# RPi_ADC_hat.net
KiCad netlist of a schematic drawn in EAGLE
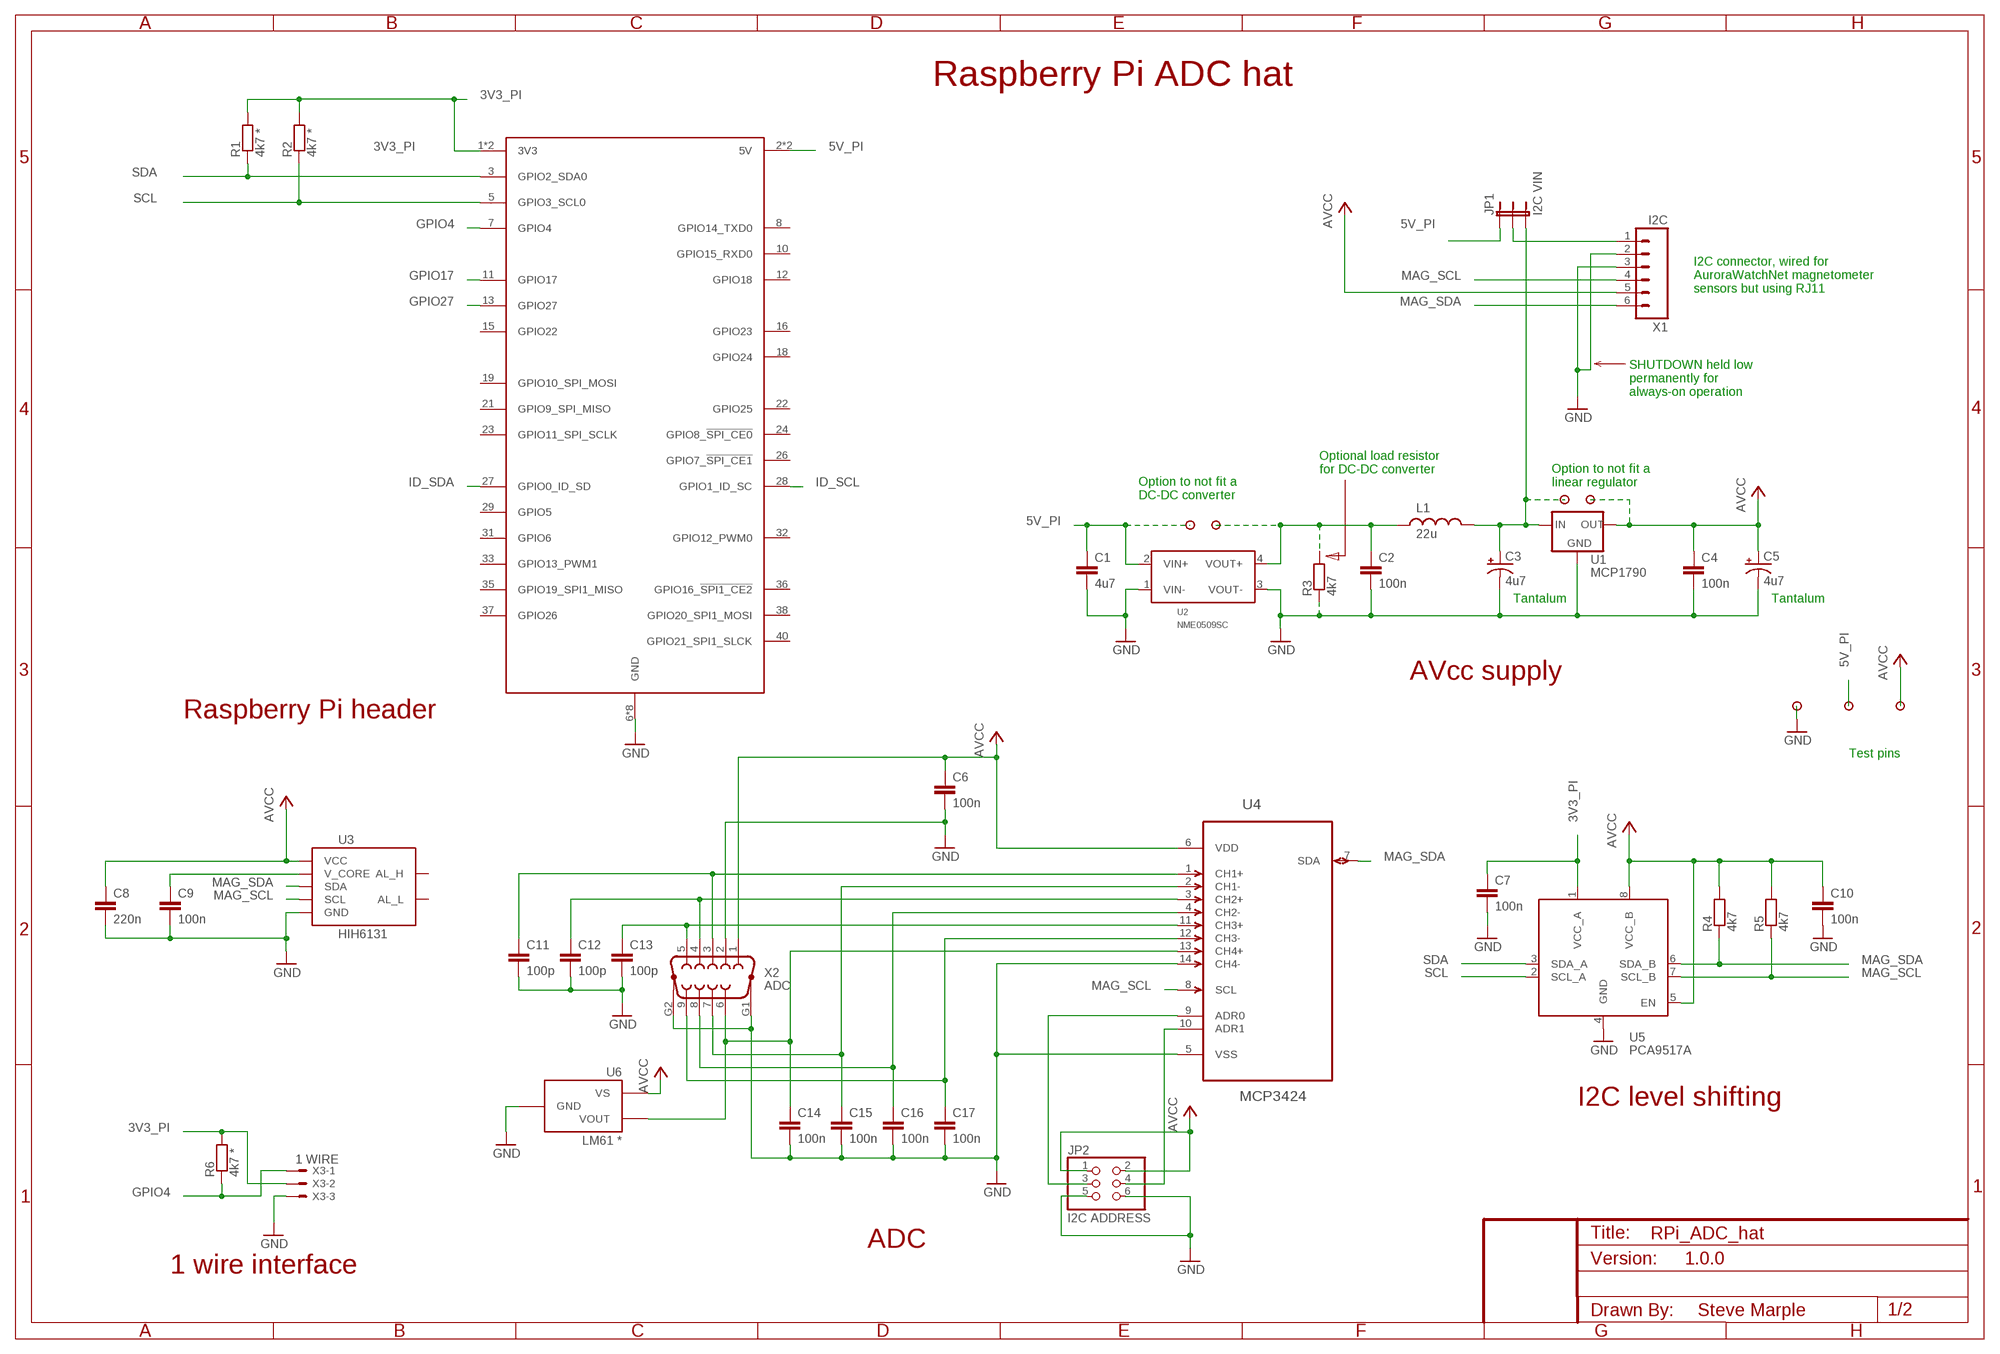
[diagram p0: schematic, sheet 1]
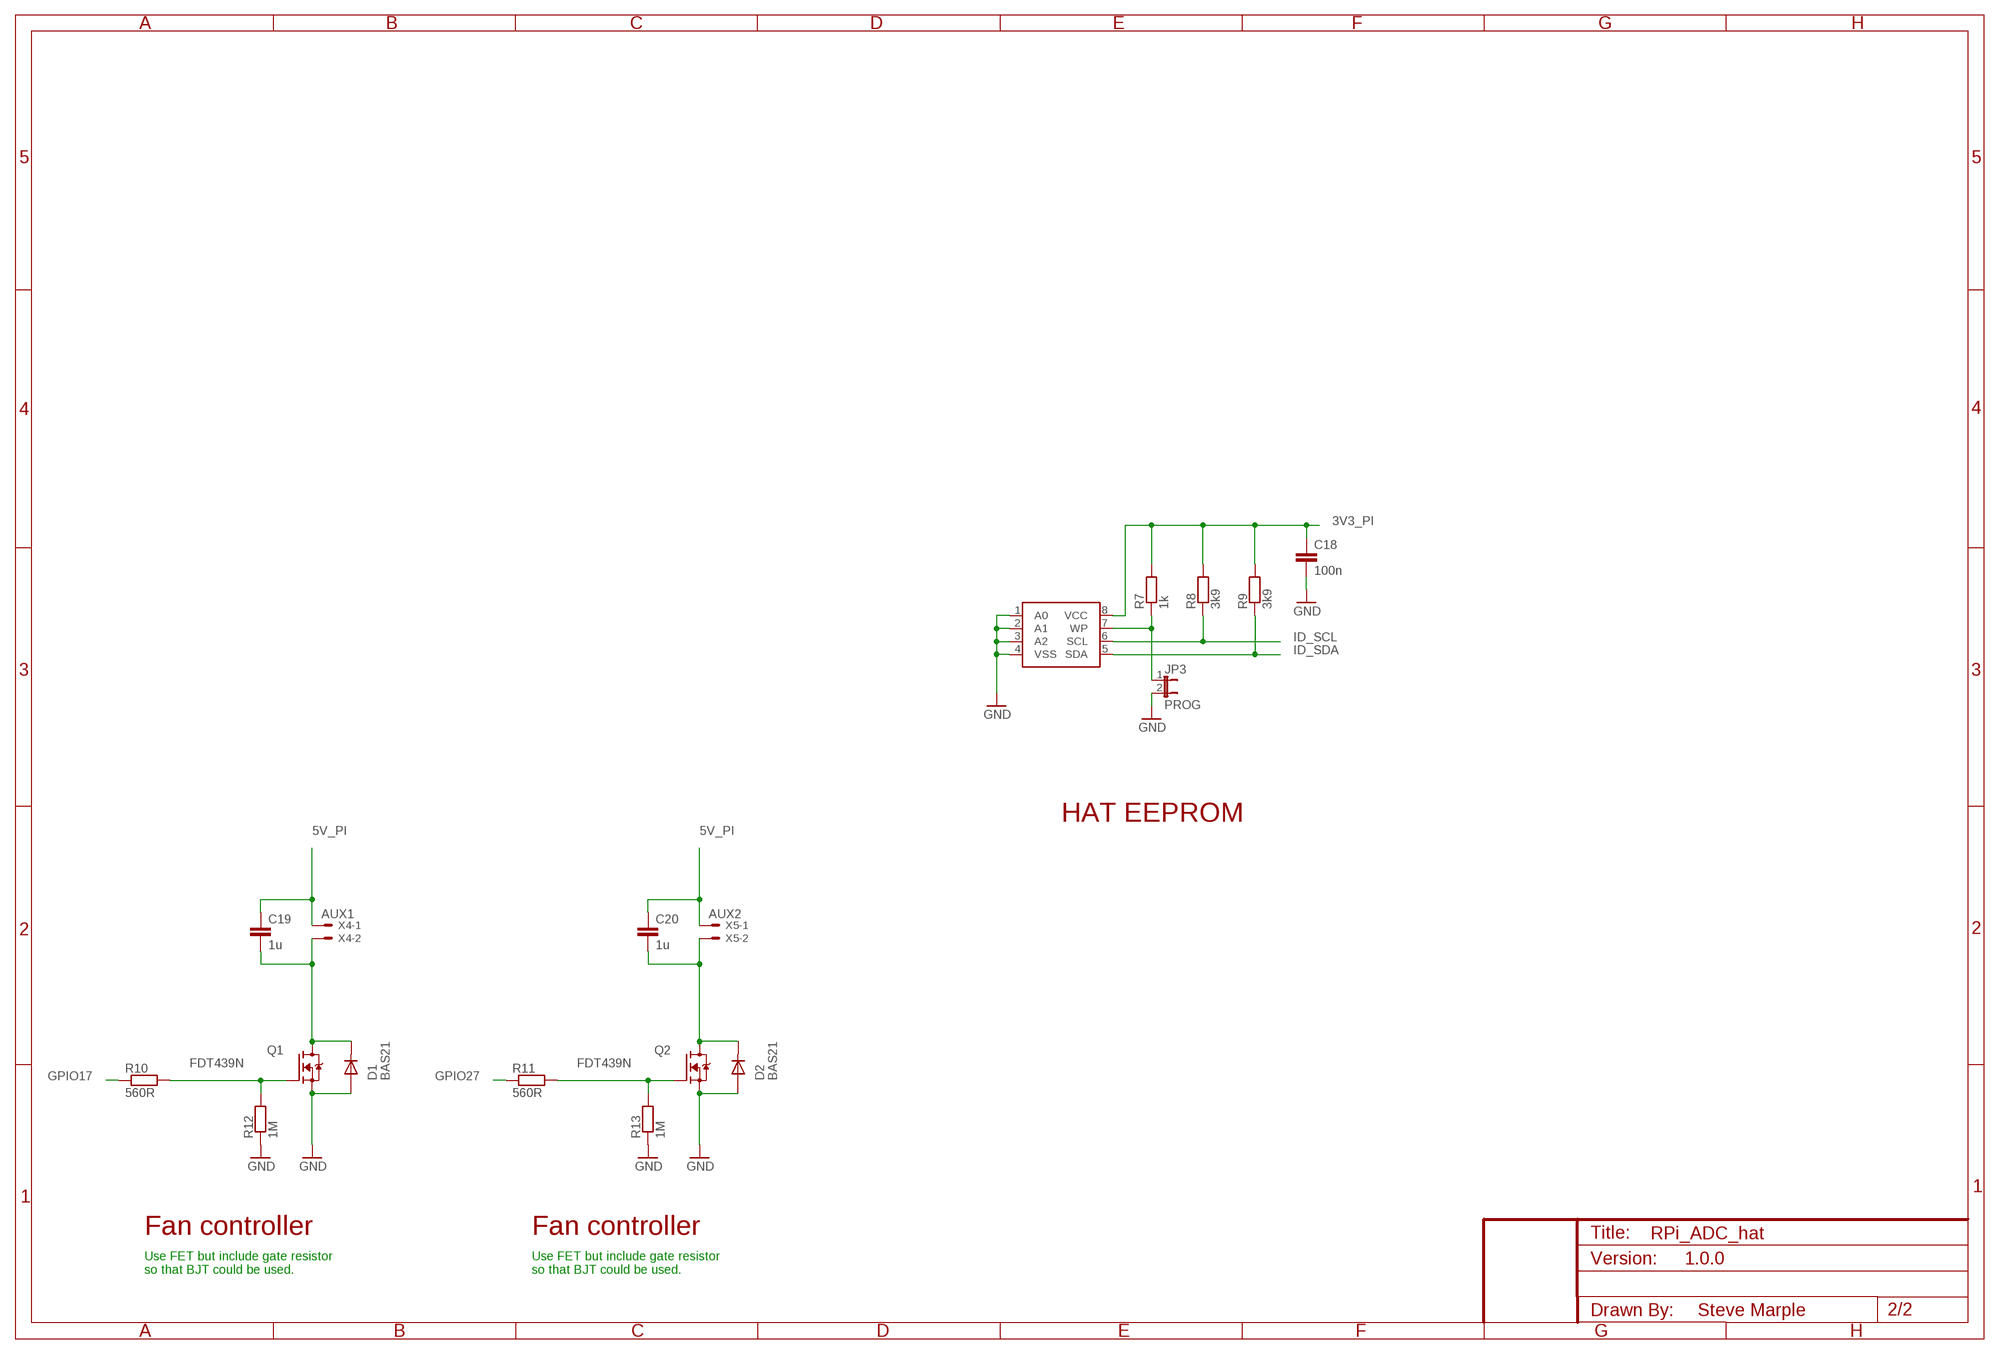
[diagram p1: schematic, sheet 2]

(export (version "E")
  (design (tool "Eeschema 10.0.6"))
  (components
    (comp (ref "C1")
      (value "4u7")
      (footprint "eagle-import:1206-HAND")
      (libsource (lib "eagle-import") (part "C-EU1206-HAND"))
    )
    (comp (ref "C2")
      (value "100n")
      (footprint "eagle-import:1206-HAND")
      (libsource (lib "eagle-import") (part "C-EU1206-HAND"))
    )
    (comp (ref "C3")
      (value "4u7")
      (footprint "eagle-import:CPOL-1210-HAND")
      (libsource (lib "eagle-import") (part "CAP_POL1210-HAND"))
    )
    (comp (ref "C4")
      (value "100n")
      (footprint "eagle-import:1206-HAND")
      (libsource (lib "eagle-import") (part "C-EU1206-HAND"))
    )
    (comp (ref "C5")
      (value "4u7")
      (footprint "eagle-import:CPOL-1210-HAND")
      (libsource (lib "eagle-import") (part "CAP_POL1210-HAND"))
    )
    (comp (ref "C6")
      (value "100n")
      (footprint "eagle-import:1206-HAND")
      (libsource (lib "eagle-import") (part "C-EU1206-HAND"))
    )
    (comp (ref "C7")
      (value "100n")
      (footprint "eagle-import:1206-HAND")
      (libsource (lib "eagle-import") (part "C-EU1206-HAND"))
    )
    (comp (ref "C8")
      (value "220n")
      (footprint "eagle-import:1206-HAND")
      (libsource (lib "eagle-import") (part "C-EU1206-HAND"))
    )
    (comp (ref "C9")
      (value "100n")
      (footprint "eagle-import:1206-HAND")
      (libsource (lib "eagle-import") (part "C-EU1206-HAND"))
    )
    (comp (ref "C10")
      (value "100n")
      (footprint "eagle-import:1206-HAND")
      (libsource (lib "eagle-import") (part "C-EU1206-HAND"))
    )
    (comp (ref "C11")
      (value "100p")
      (footprint "eagle-import:1206-HAND")
      (libsource (lib "eagle-import") (part "C-EU1206-HAND"))
    )
    (comp (ref "C12")
      (value "100p")
      (footprint "eagle-import:1206-HAND")
      (libsource (lib "eagle-import") (part "C-EU1206-HAND"))
    )
    (comp (ref "C13")
      (value "100p")
      (footprint "eagle-import:1206-HAND")
      (libsource (lib "eagle-import") (part "C-EU1206-HAND"))
    )
    (comp (ref "C14")
      (value "100n")
      (footprint "eagle-import:1206-HAND")
      (libsource (lib "eagle-import") (part "C-EU1206-HAND"))
    )
    (comp (ref "C15")
      (value "100n")
      (footprint "eagle-import:1206-HAND")
      (libsource (lib "eagle-import") (part "C-EU1206-HAND"))
    )
    (comp (ref "C16")
      (value "100n")
      (footprint "eagle-import:1206-HAND")
      (libsource (lib "eagle-import") (part "C-EU1206-HAND"))
    )
    (comp (ref "C17")
      (value "100n")
      (footprint "eagle-import:1206-HAND")
      (libsource (lib "eagle-import") (part "C-EU1206-HAND"))
    )
    (comp (ref "JP1")
      (value "I2C VIN")
      (footprint "eagle-import:1X03")
      (libsource (lib "eagle-import") (part "JUMPER-3PTH"))
    )
    (comp (ref "JP2")
      (value "I2C ADDRESS")
      (footprint "eagle-import:2X03")
      (libsource (lib "eagle-import") (part "PINHD-2X3"))
    )
    (comp (ref "L1")
      (value "22u")
      (footprint "eagle-import:1210-HAND")
      (libsource (lib "eagle-import") (part "INDUCTOR1210-HAND"))
    )
    (comp (ref "R1")
      (value "4k7 *")
      (footprint "eagle-import:1206-HAND")
      (libsource (lib "eagle-import") (part "RESISTOR1206-HAND"))
    )
    (comp (ref "R2")
      (value "4k7 *")
      (footprint "eagle-import:1206-HAND")
      (libsource (lib "eagle-import") (part "RESISTOR1206-HAND"))
    )
    (comp (ref "R3")
      (value "4k7")
      (footprint "eagle-import:1210-HAND")
      (libsource (lib "eagle-import") (part "RESISTOR1210-HAND"))
    )
    (comp (ref "R4")
      (value "4k7")
      (footprint "eagle-import:1206-HAND")
      (libsource (lib "eagle-import") (part "RESISTOR1206-HAND"))
    )
    (comp (ref "R5")
      (value "4k7")
      (footprint "eagle-import:1206-HAND")
      (libsource (lib "eagle-import") (part "RESISTOR1206-HAND"))
    )
    (comp (ref "R6")
      (value "4k7 *")
      (footprint "eagle-import:1206-HAND")
      (libsource (lib "eagle-import") (part "RESISTOR1206-HAND"))
    )
    (comp (ref "U$1")
      (value "PCB")
      (footprint "eagle-import:RASPBERRY-PI-3")
      (libsource (lib "eagle-import") (part "RASPBERRY-PI-3"))
    )
    (comp (ref "U$2")
      (value "PAD")
      (footprint "eagle-import:PAD")
      (libsource (lib "eagle-import") (part "PAD"))
    )
    (comp (ref "U$3")
      (value "PAD")
      (footprint "eagle-import:PAD")
      (libsource (lib "eagle-import") (part "PAD"))
    )
    (comp (ref "U$4")
      (value "PAD")
      (footprint "eagle-import:PAD")
      (libsource (lib "eagle-import") (part "PAD"))
    )
    (comp (ref "U$5")
      (value "PAD")
      (footprint "eagle-import:PAD")
      (libsource (lib "eagle-import") (part "PAD"))
    )
    (comp (ref "U$6")
      (value "PAD")
      (footprint "eagle-import:PAD")
      (libsource (lib "eagle-import") (part "PAD"))
    )
    (comp (ref "U$7")
      (value "PAD")
      (footprint "eagle-import:PAD")
      (libsource (lib "eagle-import") (part "PAD"))
    )
    (comp (ref "U$8")
      (value "PAD")
      (footprint "eagle-import:PAD")
      (libsource (lib "eagle-import") (part "PAD"))
    )
    (comp (ref "U1")
      (value "MCP1790")
      (footprint "eagle-import:SOT223-HAND")
      (libsource (lib "eagle-import") (part "TC1262SOT223-HAND"))
    )
    (comp (ref "U2")
      (value "NME0509SC")
      (footprint "eagle-import:DC-DC-MURATA-NME-05-12-SERIES")
      (libsource (lib "eagle-import") (part "DC-DC-CONV-4PIN-ISOLATINGMURATA-NME-05-12-SERIES"))
    )
    (comp (ref "U3")
      (value "HIH6131")
      (footprint "eagle-import:SO08")
      (libsource (lib "eagle-import") (part "HONEYWELL-HIH613XSOIC8"))
    )
    (comp (ref "U4")
      (value "MCP3424")
      (footprint "eagle-import:SO14")
      (libsource (lib "eagle-import") (part "MCP3424-E/SLSO14"))
    )
    (comp (ref "U5")
      (value "PCA9517A")
      (footprint "eagle-import:SO08")
      (libsource (lib "eagle-import") (part "PCA9517ASOIC"))
    )
    (comp (ref "U6")
      (value "LM61 *")
      (footprint "eagle-import:SOT23-3-HAND")
      (libsource (lib "eagle-import") (part "LM61SOT23"))
    )
    (comp (ref "X1")
      (value "I2C")
      (footprint "eagle-import:RJ11-6")
      (libsource (lib "eagle-import") (part "RJ11-6PTH"))
    )
    (comp (ref "X2")
      (value "ADC")
      (footprint "eagle-import:DSUB-5504F1-02-9PIN")
      (libsource (lib "eagle-import") (part "CONN-D9-FEMALEMULTICOMP-5504F1"))
    )
    (comp (ref "X3")
      (value "1 WIRE")
      (footprint "eagle-import:22-23-2031")
      (fields (field (name "MF") "MOLEX") (field (name "MPN") "22-23-2031"))
      (libsource (lib "eagle-import") (part "22-23-2031"))
    )
    (comp (ref "C18")
      (value "100n")
      (footprint "eagle-import:1206-HAND")
      (libsource (lib "eagle-import") (part "C-EU1206-HAND"))
    )
    (comp (ref "C19")
      (value "1u")
      (footprint "eagle-import:1206-HAND")
      (libsource (lib "eagle-import") (part "C-EU1206-HAND"))
    )
    (comp (ref "C20")
      (value "1u")
      (footprint "eagle-import:1206-HAND")
      (libsource (lib "eagle-import") (part "C-EU1206-HAND"))
    )
    (comp (ref "D1")
      (value "BAS21")
      (footprint "eagle-import:SOT23-3-HAND")
      (libsource (lib "eagle-import") (part "DIODESOT23-1-3-HAND"))
    )
    (comp (ref "D2")
      (value "BAS21")
      (footprint "eagle-import:SOT23-3-HAND")
      (libsource (lib "eagle-import") (part "DIODESOT23-1-3-HAND"))
    )
    (comp (ref "JP3")
      (value "PROG")
      (footprint "eagle-import:1X02")
      (libsource (lib "eagle-import") (part "JUMPER-2PTH"))
    )
    (comp (ref "Q1")
      (value "FDT439N")
      (footprint "eagle-import:SOT223-HAND")
      (libsource (lib "eagle-import") (part "FET-N-TYPESOT223-HAND"))
    )
    (comp (ref "Q2")
      (value "FDT439N")
      (footprint "eagle-import:SOT223-HAND")
      (libsource (lib "eagle-import") (part "FET-N-TYPESOT223-HAND"))
    )
    (comp (ref "R7")
      (value "1k")
      (footprint "eagle-import:1206-HAND")
      (libsource (lib "eagle-import") (part "RESISTOR1206-HAND"))
    )
    (comp (ref "R8")
      (value "3k9")
      (footprint "eagle-import:1206-HAND")
      (libsource (lib "eagle-import") (part "RESISTOR1206-HAND"))
    )
    (comp (ref "R9")
      (value "3k9")
      (footprint "eagle-import:1206-HAND")
      (libsource (lib "eagle-import") (part "RESISTOR1206-HAND"))
    )
    (comp (ref "R10")
      (value "560R")
      (footprint "eagle-import:1206-HAND")
      (libsource (lib "eagle-import") (part "RESISTOR1206-HAND"))
    )
    (comp (ref "R11")
      (value "560R")
      (footprint "eagle-import:1206-HAND")
      (libsource (lib "eagle-import") (part "RESISTOR1206-HAND"))
    )
    (comp (ref "R12")
      (value "1M")
      (footprint "eagle-import:1206-HAND")
      (libsource (lib "eagle-import") (part "RESISTOR1206-HAND"))
    )
    (comp (ref "R13")
      (value "1M")
      (footprint "eagle-import:1206-HAND")
      (libsource (lib "eagle-import") (part "RESISTOR1206-HAND"))
    )
    (comp (ref "U7")
      (value "C24C32")
      (footprint "eagle-import:SO08")
      (libsource (lib "eagle-import") (part "EEPROM-C24CXXSOIC8"))
    )
    (comp (ref "X4")
      (value "AUX1")
      (footprint "eagle-import:22-23-2021")
      (fields (field (name "MF") "MOLEX") (field (name "MPN") "22-23-2021"))
      (libsource (lib "eagle-import") (part "22-23-2021"))
    )
    (comp (ref "X5")
      (value "AUX2")
      (footprint "eagle-import:22-23-2021")
      (fields (field (name "MF") "MOLEX") (field (name "MPN") "22-23-2021"))
      (libsource (lib "eagle-import") (part "22-23-2021"))
    )
  )
  (nets
    (net (code "1") (name "3V3_PI") (class "Default")
      (node (ref "C18") (pin "1") (pinfunction "1_1") (pintype "passive"))
      (node (ref "C7") (pin "1") (pinfunction "1_1") (pintype "passive"))
      (node (ref "R1") (pin "2") (pinfunction "2_2") (pintype "passive"))
      (node (ref "R2") (pin "2") (pinfunction "2_2") (pintype "passive"))
      (node (ref "R6") (pin "2") (pinfunction "2_2") (pintype "passive"))
      (node (ref "R7") (pin "2") (pinfunction "2_2") (pintype "passive"))
      (node (ref "R8") (pin "2") (pinfunction "2_2") (pintype "passive"))
      (node (ref "R9") (pin "2") (pinfunction "2_2") (pintype "passive"))
      (node (ref "U$1") (pin "1") (pinfunction "3V3_1") (pintype "bidirectional"))
      (node (ref "U$1") (pin "17") (pinfunction "3V3_17") (pintype "bidirectional"))
      (node (ref "U5") (pin "1") (pinfunction "VCC_A_1") (pintype "power_in"))
      (node (ref "U7") (pin "8") (pinfunction "VCC_8") (pintype "power_in"))
      (node (ref "X3") (pin "2") (pinfunction "S_2") (pintype "passive"))
    )
    (net (code "2") (name "5V_PI") (class "Default")
      (node (ref "C1") (pin "1") (pinfunction "1_1") (pintype "passive"))
      (node (ref "C19") (pin "1") (pinfunction "1_1") (pintype "passive"))
      (node (ref "C20") (pin "1") (pinfunction "1_1") (pintype "passive"))
      (node (ref "JP1") (pin "1") (pinfunction "1_1") (pintype "passive"))
      (node (ref "U$1") (pin "2") (pinfunction "5V_2") (pintype "bidirectional"))
      (node (ref "U$1") (pin "4") (pinfunction "5V_4") (pintype "bidirectional"))
      (node (ref "U$4") (pin "1") (pinfunction "1_1") (pintype "bidirectional"))
      (node (ref "U$7") (pin "1") (pinfunction "1_1") (pintype "bidirectional"))
      (node (ref "U2") (pin "2") (pinfunction "VIN+_2") (pintype "bidirectional"))
      (node (ref "X4") (pin "1") (pinfunction "S_1") (pintype "passive"))
      (node (ref "X5") (pin "1") (pinfunction "S_1") (pintype "passive"))
    )
    (net (code "3") (name "AVCC") (class "Default")
      (node (ref "C10") (pin "1") (pinfunction "1_1") (pintype "passive"))
      (node (ref "C4") (pin "1") (pinfunction "1_1") (pintype "passive"))
      (node (ref "C5") (pin "+") (pinfunction "+_+") (pintype "passive"))
      (node (ref "C6") (pin "1") (pinfunction "1_1") (pintype "passive"))
      (node (ref "C8") (pin "1") (pinfunction "1_1") (pintype "passive"))
      (node (ref "JP2") (pin "1") (pinfunction "1_1") (pintype "passive"))
      (node (ref "JP2") (pin "2") (pinfunction "2_2") (pintype "passive"))
      (node (ref "R4") (pin "2") (pinfunction "2_2") (pintype "passive"))
      (node (ref "R5") (pin "2") (pinfunction "2_2") (pintype "passive"))
      (node (ref "U$3") (pin "1") (pinfunction "1_1") (pintype "bidirectional"))
      (node (ref "U$8") (pin "1") (pinfunction "1_1") (pintype "bidirectional"))
      (node (ref "U1") (pin "3") (pinfunction "OUT_3") (pintype "power_in"))
      (node (ref "U3") (pin "8") (pinfunction "VCC_8") (pintype "power_in"))
      (node (ref "U4") (pin "6") (pinfunction "VDD_6") (pintype "power_in"))
      (node (ref "U5") (pin "5") (pinfunction "EN_5") (pintype "bidirectional"))
      (node (ref "U5") (pin "8") (pinfunction "VCC_B_8") (pintype "power_in"))
      (node (ref "U6") (pin "1") (pinfunction "VS_1") (pintype "bidirectional"))
      (node (ref "X1") (pin "5") (pinfunction "5_5") (pintype "passive"))
      (node (ref "X2") (pin "1") (pinfunction "1_1") (pintype "passive"))
    )
    (net (code "4") (name "GND") (class "Default")
      (node (ref "C1") (pin "2") (pinfunction "2_2") (pintype "passive"))
      (node (ref "C10") (pin "2") (pinfunction "2_2") (pintype "passive"))
      (node (ref "C11") (pin "2") (pinfunction "2_2") (pintype "passive"))
      (node (ref "C12") (pin "2") (pinfunction "2_2") (pintype "passive"))
      (node (ref "C13") (pin "2") (pinfunction "2_2") (pintype "passive"))
      (node (ref "C14") (pin "2") (pinfunction "2_2") (pintype "passive"))
      (node (ref "C15") (pin "2") (pinfunction "2_2") (pintype "passive"))
      (node (ref "C16") (pin "2") (pinfunction "2_2") (pintype "passive"))
      (node (ref "C17") (pin "2") (pinfunction "2_2") (pintype "passive"))
      (node (ref "C18") (pin "2") (pinfunction "2_2") (pintype "passive"))
      (node (ref "C2") (pin "2") (pinfunction "2_2") (pintype "passive"))
      (node (ref "C3") (pin "-") (pinfunction "-_-") (pintype "passive"))
      (node (ref "C4") (pin "2") (pinfunction "2_2") (pintype "passive"))
      (node (ref "C5") (pin "-") (pinfunction "-_-") (pintype "passive"))
      (node (ref "C6") (pin "2") (pinfunction "2_2") (pintype "passive"))
      (node (ref "C7") (pin "2") (pinfunction "2_2") (pintype "passive"))
      (node (ref "C8") (pin "2") (pinfunction "2_2") (pintype "passive"))
      (node (ref "C9") (pin "2") (pinfunction "2_2") (pintype "passive"))
      (node (ref "D1") (pin "1") (pinfunction "A_1") (pintype "passive"))
      (node (ref "D2") (pin "1") (pinfunction "A_1") (pintype "passive"))
      (node (ref "JP2") (pin "5") (pinfunction "5_5") (pintype "passive"))
      (node (ref "JP2") (pin "6") (pinfunction "6_6") (pintype "passive"))
      (node (ref "JP3") (pin "2") (pinfunction "2_2") (pintype "passive"))
      (node (ref "Q1") (pin "3") (pinfunction "S_3") (pintype "passive"))
      (node (ref "Q2") (pin "3") (pinfunction "S_3") (pintype "passive"))
      (node (ref "R12") (pin "1") (pinfunction "1_1") (pintype "passive"))
      (node (ref "R13") (pin "1") (pinfunction "1_1") (pintype "passive"))
      (node (ref "R3") (pin "1") (pinfunction "1_1") (pintype "passive"))
      (node (ref "U$1") (pin "14") (pinfunction "GND_14") (pintype "bidirectional"))
      (node (ref "U$1") (pin "20") (pinfunction "GND_20") (pintype "bidirectional"))
      (node (ref "U$1") (pin "25") (pinfunction "GND_25") (pintype "bidirectional"))
      (node (ref "U$1") (pin "30") (pinfunction "GND_30") (pintype "bidirectional"))
      (node (ref "U$1") (pin "34") (pinfunction "GND_34") (pintype "bidirectional"))
      (node (ref "U$1") (pin "39") (pinfunction "GND_39") (pintype "bidirectional"))
      (node (ref "U$1") (pin "6") (pinfunction "GND_6") (pintype "bidirectional"))
      (node (ref "U$1") (pin "9") (pinfunction "GND_9") (pintype "bidirectional"))
      (node (ref "U$6") (pin "1") (pinfunction "1_1") (pintype "bidirectional"))
      (node (ref "U1") (pin "2") (pinfunction "GND_2") (pintype "power_in"))
      (node (ref "U1") (pin "4") (pinfunction "GND_4") (pintype "power_in"))
      (node (ref "U2") (pin "1") (pinfunction "VIN-_1") (pintype "bidirectional"))
      (node (ref "U2") (pin "3") (pinfunction "VOUT-_3") (pintype "bidirectional"))
      (node (ref "U3") (pin "2") (pinfunction "GND_2") (pintype "power_in"))
      (node (ref "U4") (pin "14") (pinfunction "CH4-_14") (pintype "input"))
      (node (ref "U4") (pin "5") (pinfunction "VSS_5") (pintype "power_in"))
      (node (ref "U5") (pin "4") (pinfunction "GND_4") (pintype "power_in"))
      (node (ref "U6") (pin "3") (pinfunction "GND_3") (pintype "bidirectional"))
      (node (ref "U7") (pin "1") (pinfunction "A0_1") (pintype "input"))
      (node (ref "U7") (pin "2") (pinfunction "A1_2") (pintype "input"))
      (node (ref "U7") (pin "3") (pinfunction "A2_3") (pintype "input"))
      (node (ref "U7") (pin "4") (pinfunction "VSS_4") (pintype "power_in"))
      (node (ref "X1") (pin "2") (pinfunction "2_2") (pintype "passive"))
      (node (ref "X1") (pin "3") (pinfunction "3_3") (pintype "passive"))
      (node (ref "X2") (pin "2") (pinfunction "2_2") (pintype "passive"))
      (node (ref "X2") (pin "G1") (pinfunction "G1_G1") (pintype "passive"))
      (node (ref "X2") (pin "G2") (pinfunction "G2_G2") (pintype "passive"))
      (node (ref "X3") (pin "3") (pinfunction "S_3") (pintype "passive"))
    )
    (net (code "5") (name "GPIO4") (class "Default")
      (node (ref "R6") (pin "1") (pinfunction "1_1") (pintype "passive"))
      (node (ref "U$1") (pin "7") (pinfunction "GPIO4_7") (pintype "bidirectional"))
      (node (ref "X3") (pin "1") (pinfunction "S_1") (pintype "passive"))
    )
    (net (code "6") (name "GPIO17") (class "Default")
      (node (ref "R10") (pin "1") (pinfunction "1_1") (pintype "passive"))
      (node (ref "U$1") (pin "11") (pinfunction "GPIO17_11") (pintype "bidirectional"))
    )
    (net (code "7") (name "GPIO27") (class "Default")
      (node (ref "R11") (pin "1") (pinfunction "1_1") (pintype "passive"))
      (node (ref "U$1") (pin "13") (pinfunction "GPIO27_13") (pintype "bidirectional"))
    )
    (net (code "8") (name "ID_SCL") (class "Default")
      (node (ref "R8") (pin "1") (pinfunction "1_1") (pintype "passive"))
      (node (ref "U$1") (pin "28") (pinfunction "GPIO1_ID_SC_28") (pintype "bidirectional"))
      (node (ref "U7") (pin "6") (pinfunction "SCL_6") (pintype "bidirectional"))
    )
    (net (code "9") (name "ID_SDA") (class "Default")
      (node (ref "R9") (pin "1") (pinfunction "1_1") (pintype "passive"))
      (node (ref "U$1") (pin "27") (pinfunction "GPIO0_ID_SD_27") (pintype "bidirectional"))
      (node (ref "U7") (pin "5") (pinfunction "SDA_5") (pintype "bidirectional"))
    )
    (net (code "10") (name "MAG_SCL") (class "Default")
      (node (ref "R5") (pin "1") (pinfunction "1_1") (pintype "passive"))
      (node (ref "U3") (pin "3") (pinfunction "SCL_3") (pintype "bidirectional"))
      (node (ref "U4") (pin "8") (pinfunction "SCL_8") (pintype "input"))
      (node (ref "U5") (pin "7") (pinfunction "SCL_B_7") (pintype "bidirectional"))
      (node (ref "X1") (pin "4") (pinfunction "4_4") (pintype "passive"))
    )
    (net (code "11") (name "MAG_SDA") (class "Default")
      (node (ref "R4") (pin "1") (pinfunction "1_1") (pintype "passive"))
      (node (ref "U3") (pin "4") (pinfunction "SDA_4") (pintype "bidirectional"))
      (node (ref "U4") (pin "7") (pinfunction "SDA_7") (pintype "bidirectional"))
      (node (ref "U5") (pin "6") (pinfunction "SDA_B_6") (pintype "bidirectional"))
      (node (ref "X1") (pin "6") (pinfunction "6_6") (pintype "passive"))
    )
    (net (code "12") (name "Net-(D1-C)") (class "Default")
      (node (ref "C19") (pin "2") (pinfunction "2_2") (pintype "passive"))
      (node (ref "D1") (pin "3") (pinfunction "C_3") (pintype "passive"))
      (node (ref "Q1") (pin "2") (pinfunction "D_2") (pintype "passive"))
      (node (ref "Q1") (pin "4") (pinfunction "D_4") (pintype "passive"))
      (node (ref "X4") (pin "2") (pinfunction "S_2") (pintype "passive"))
    )
    (net (code "13") (name "Net-(D2-C)") (class "Default")
      (node (ref "C20") (pin "2") (pinfunction "2_2") (pintype "passive"))
      (node (ref "D2") (pin "3") (pinfunction "C_3") (pintype "passive"))
      (node (ref "Q2") (pin "2") (pinfunction "D_2") (pintype "passive"))
      (node (ref "Q2") (pin "4") (pinfunction "D_4") (pintype "passive"))
      (node (ref "X5") (pin "2") (pinfunction "S_2") (pintype "passive"))
    )
    (net (code "14") (name "Net-(JP1-Pad2)") (class "Default")
      (node (ref "JP1") (pin "2") (pinfunction "2_2") (pintype "passive"))
      (node (ref "X1") (pin "1") (pinfunction "1_1") (pintype "passive"))
    )
    (net (code "15") (name "Net-(Q1-G)") (class "Default")
      (node (ref "Q1") (pin "1") (pinfunction "G_1") (pintype "passive"))
      (node (ref "R10") (pin "2") (pinfunction "2_2") (pintype "passive"))
      (node (ref "R12") (pin "2") (pinfunction "2_2") (pintype "passive"))
    )
    (net (code "16") (name "Net-(Q2-G)") (class "Default")
      (node (ref "Q2") (pin "1") (pinfunction "G_1") (pintype "passive"))
      (node (ref "R11") (pin "2") (pinfunction "2_2") (pintype "passive"))
      (node (ref "R13") (pin "2") (pinfunction "2_2") (pintype "passive"))
    )
    (net (code "17") (name "Net-(U1-IN)") (class "Default")
      (node (ref "C3") (pin "+") (pinfunction "+_+") (pintype "passive"))
      (node (ref "JP1") (pin "3") (pinfunction "3_3") (pintype "passive"))
      (node (ref "L1") (pin "2") (pinfunction "2_2") (pintype "passive"))
      (node (ref "U$2") (pin "1") (pinfunction "1_1") (pintype "bidirectional"))
      (node (ref "U1") (pin "1") (pinfunction "IN_1") (pintype "input"))
    )
    (net (code "18") (name "Net-(U2-VOUT+)") (class "Default")
      (node (ref "C2") (pin "1") (pinfunction "1_1") (pintype "passive"))
      (node (ref "L1") (pin "1") (pinfunction "1_1") (pintype "passive"))
      (node (ref "R3") (pin "2") (pinfunction "2_2") (pintype "passive"))
      (node (ref "U$5") (pin "1") (pinfunction "1_1") (pintype "bidirectional"))
      (node (ref "U2") (pin "4") (pinfunction "VOUT+_4") (pintype "bidirectional"))
    )
    (net (code "19") (name "Net-(U3-V_CORE)") (class "Default")
      (node (ref "C9") (pin "1") (pinfunction "1_1") (pintype "passive"))
      (node (ref "U3") (pin "1") (pinfunction "V_CORE_1") (pintype "output"))
    )
    (net (code "20") (name "Net-(U4-ADR0)") (class "Default")
      (node (ref "JP2") (pin "3") (pinfunction "3_3") (pintype "passive"))
      (node (ref "U4") (pin "9") (pinfunction "ADR0_9") (pintype "input"))
    )
    (net (code "21") (name "Net-(U4-ADR1)") (class "Default")
      (node (ref "JP2") (pin "4") (pinfunction "4_4") (pintype "passive"))
      (node (ref "U4") (pin "10") (pinfunction "ADR1_10") (pintype "input"))
    )
    (net (code "22") (name "Net-(U4-CH1+)") (class "Default")
      (node (ref "C11") (pin "1") (pinfunction "1_1") (pintype "passive"))
      (node (ref "U4") (pin "1") (pinfunction "CH1+_1") (pintype "input"))
      (node (ref "X2") (pin "3") (pinfunction "3_3") (pintype "passive"))
    )
    (net (code "23") (name "Net-(U4-CH1-)") (class "Default")
      (node (ref "C15") (pin "1") (pinfunction "1_1") (pintype "passive"))
      (node (ref "U4") (pin "2") (pinfunction "CH1-_2") (pintype "input"))
      (node (ref "X2") (pin "7") (pinfunction "7_7") (pintype "passive"))
    )
    (net (code "24") (name "Net-(U4-CH2+)") (class "Default")
      (node (ref "C12") (pin "1") (pinfunction "1_1") (pintype "passive"))
      (node (ref "U4") (pin "3") (pinfunction "CH2+_3") (pintype "input"))
      (node (ref "X2") (pin "4") (pinfunction "4_4") (pintype "passive"))
    )
    (net (code "25") (name "Net-(U4-CH2-)") (class "Default")
      (node (ref "C16") (pin "1") (pinfunction "1_1") (pintype "passive"))
      (node (ref "U4") (pin "4") (pinfunction "CH2-_4") (pintype "input"))
      (node (ref "X2") (pin "8") (pinfunction "8_8") (pintype "passive"))
    )
    (net (code "26") (name "Net-(U4-CH3+)") (class "Default")
      (node (ref "C13") (pin "1") (pinfunction "1_1") (pintype "passive"))
      (node (ref "U4") (pin "11") (pinfunction "CH3+_11") (pintype "input"))
      (node (ref "X2") (pin "5") (pinfunction "5_5") (pintype "passive"))
    )
    (net (code "27") (name "Net-(U4-CH3-)") (class "Default")
      (node (ref "C17") (pin "1") (pinfunction "1_1") (pintype "passive"))
      (node (ref "U4") (pin "12") (pinfunction "CH3-_12") (pintype "input"))
      (node (ref "X2") (pin "9") (pinfunction "9_9") (pintype "passive"))
    )
    (net (code "28") (name "Net-(U4-CH4+)") (class "Default")
      (node (ref "C14") (pin "1") (pinfunction "1_1") (pintype "passive"))
      (node (ref "U4") (pin "13") (pinfunction "CH4+_13") (pintype "input"))
      (node (ref "U6") (pin "2") (pinfunction "VOUT_2") (pintype "bidirectional"))
      (node (ref "X2") (pin "6") (pinfunction "6_6") (pintype "passive"))
    )
    (net (code "29") (name "Net-(U7-WP)") (class "Default")
      (node (ref "JP3") (pin "1") (pinfunction "1_1") (pintype "passive"))
      (node (ref "R7") (pin "1") (pinfunction "1_1") (pintype "passive"))
      (node (ref "U7") (pin "7") (pinfunction "WP_7") (pintype "input"))
    )
    (net (code "30") (name "SCL") (class "Default")
      (node (ref "R2") (pin "1") (pinfunction "1_1") (pintype "passive"))
      (node (ref "U$1") (pin "5") (pinfunction "GPIO3_SCL0_5") (pintype "bidirectional"))
      (node (ref "U5") (pin "2") (pinfunction "SCL_A_2") (pintype "bidirectional"))
    )
    (net (code "31") (name "SDA") (class "Default")
      (node (ref "R1") (pin "1") (pinfunction "1_1") (pintype "passive"))
      (node (ref "U$1") (pin "3") (pinfunction "GPIO2_SDA0_3") (pintype "bidirectional"))
      (node (ref "U5") (pin "3") (pinfunction "SDA_A_3") (pintype "bidirectional"))
    )
    (net (code "32") (name "unconnected-(U$1-GPIO5-Pad29)") (class "Default")
      (node (ref "U$1") (pin "29") (pinfunction "GPIO5_29") (pintype "bidirectional"))
    )
    (net (code "33") (name "unconnected-(U$1-GPIO6-Pad31)") (class "Default")
      (node (ref "U$1") (pin "31") (pinfunction "GPIO6_31") (pintype "bidirectional"))
    )
    (net (code "34") (name "unconnected-(U$1-GPIO7_~{SPI_CE1}-Pad26)") (class "Default")
      (node (ref "U$1") (pin "26") (pinfunction "GPIO7_~{SPI_CE1}_26") (pintype "bidirectional"))
    )
    (net (code "35") (name "unconnected-(U$1-GPIO8_~{SPI_CE0}-Pad24)") (class "Default")
      (node (ref "U$1") (pin "24") (pinfunction "GPIO8_~{SPI_CE0}_24") (pintype "bidirectional"))
    )
    (net (code "36") (name "unconnected-(U$1-GPIO9_SPI_MISO-Pad21)") (class "Default")
      (node (ref "U$1") (pin "21") (pinfunction "GPIO9_SPI_MISO_21") (pintype "bidirectional"))
    )
    (net (code "37") (name "unconnected-(U$1-GPIO10_SPI_MOSI-Pad19)") (class "Default")
      (node (ref "U$1") (pin "19") (pinfunction "GPIO10_SPI_MOSI_19") (pintype "bidirectional"))
    )
    (net (code "38") (name "unconnected-(U$1-GPIO11_SPI_SCLK-Pad23)") (class "Default")
      (node (ref "U$1") (pin "23") (pinfunction "GPIO11_SPI_SCLK_23") (pintype "bidirectional"))
    )
    (net (code "39") (name "unconnected-(U$1-GPIO12_PWM0-Pad32)") (class "Default")
      (node (ref "U$1") (pin "32") (pinfunction "GPIO12_PWM0_32") (pintype "bidirectional"))
    )
    (net (code "40") (name "unconnected-(U$1-GPIO13_PWM1-Pad33)") (class "Default")
      (node (ref "U$1") (pin "33") (pinfunction "GPIO13_PWM1_33") (pintype "bidirectional"))
    )
    (net (code "41") (name "unconnected-(U$1-GPIO14_TXD0-Pad8)") (class "Default")
      (node (ref "U$1") (pin "8") (pinfunction "GPIO14_TXD0_8") (pintype "bidirectional"))
    )
    (net (code "42") (name "unconnected-(U$1-GPIO15_RXD0-Pad10)") (class "Default")
      (node (ref "U$1") (pin "10") (pinfunction "GPIO15_RXD0_10") (pintype "bidirectional"))
    )
    (net (code "43") (name "unconnected-(U$1-GPIO16_~{SPI1_CE2}-Pad36)") (class "Default")
      (node (ref "U$1") (pin "36") (pinfunction "GPIO16_~{SPI1_CE2}_36") (pintype "bidirectional"))
    )
    (net (code "44") (name "unconnected-(U$1-GPIO18-Pad12)") (class "Default")
      (node (ref "U$1") (pin "12") (pinfunction "GPIO18_12") (pintype "bidirectional"))
    )
    (net (code "45") (name "unconnected-(U$1-GPIO19_SPI1_MISO-Pad35)") (class "Default")
      (node (ref "U$1") (pin "35") (pinfunction "GPIO19_SPI1_MISO_35") (pintype "bidirectional"))
    )
    (net (code "46") (name "unconnected-(U$1-GPIO20_SPI1_MOSI-Pad38)") (class "Default")
      (node (ref "U$1") (pin "38") (pinfunction "GPIO20_SPI1_MOSI_38") (pintype "bidirectional"))
    )
    (net (code "47") (name "unconnected-(U$1-GPIO21_SPI1_SLCK-Pad40)") (class "Default")
      (node (ref "U$1") (pin "40") (pinfunction "GPIO21_SPI1_SLCK_40") (pintype "bidirectional"))
    )
    (net (code "48") (name "unconnected-(U$1-GPIO22-Pad15)") (class "Default")
      (node (ref "U$1") (pin "15") (pinfunction "GPIO22_15") (pintype "bidirectional"))
    )
    (net (code "49") (name "unconnected-(U$1-GPIO23-Pad16)") (class "Default")
      (node (ref "U$1") (pin "16") (pinfunction "GPIO23_16") (pintype "bidirectional"))
    )
    (net (code "50") (name "unconnected-(U$1-GPIO24-Pad18)") (class "Default")
      (node (ref "U$1") (pin "18") (pinfunction "GPIO24_18") (pintype "bidirectional"))
    )
    (net (code "51") (name "unconnected-(U$1-GPIO25-Pad22)") (class "Default")
      (node (ref "U$1") (pin "22") (pinfunction "GPIO25_22") (pintype "bidirectional"))
    )
    (net (code "52") (name "unconnected-(U$1-GPIO26-Pad37)") (class "Default")
      (node (ref "U$1") (pin "37") (pinfunction "GPIO26_37") (pintype "bidirectional"))
    )
    (net (code "53") (name "unconnected-(U3-AL_H-Pad5)") (class "Default")
      (node (ref "U3") (pin "5") (pinfunction "AL_H_5") (pintype "bidirectional"))
    )
    (net (code "54") (name "unconnected-(U3-AL_L-Pad6)") (class "Default")
      (node (ref "U3") (pin "6") (pinfunction "AL_L_6") (pintype "bidirectional"))
    )
  )
)
